# Aux_Outputs.net
KiCad netlist of a schematic drawn in Altium Designer
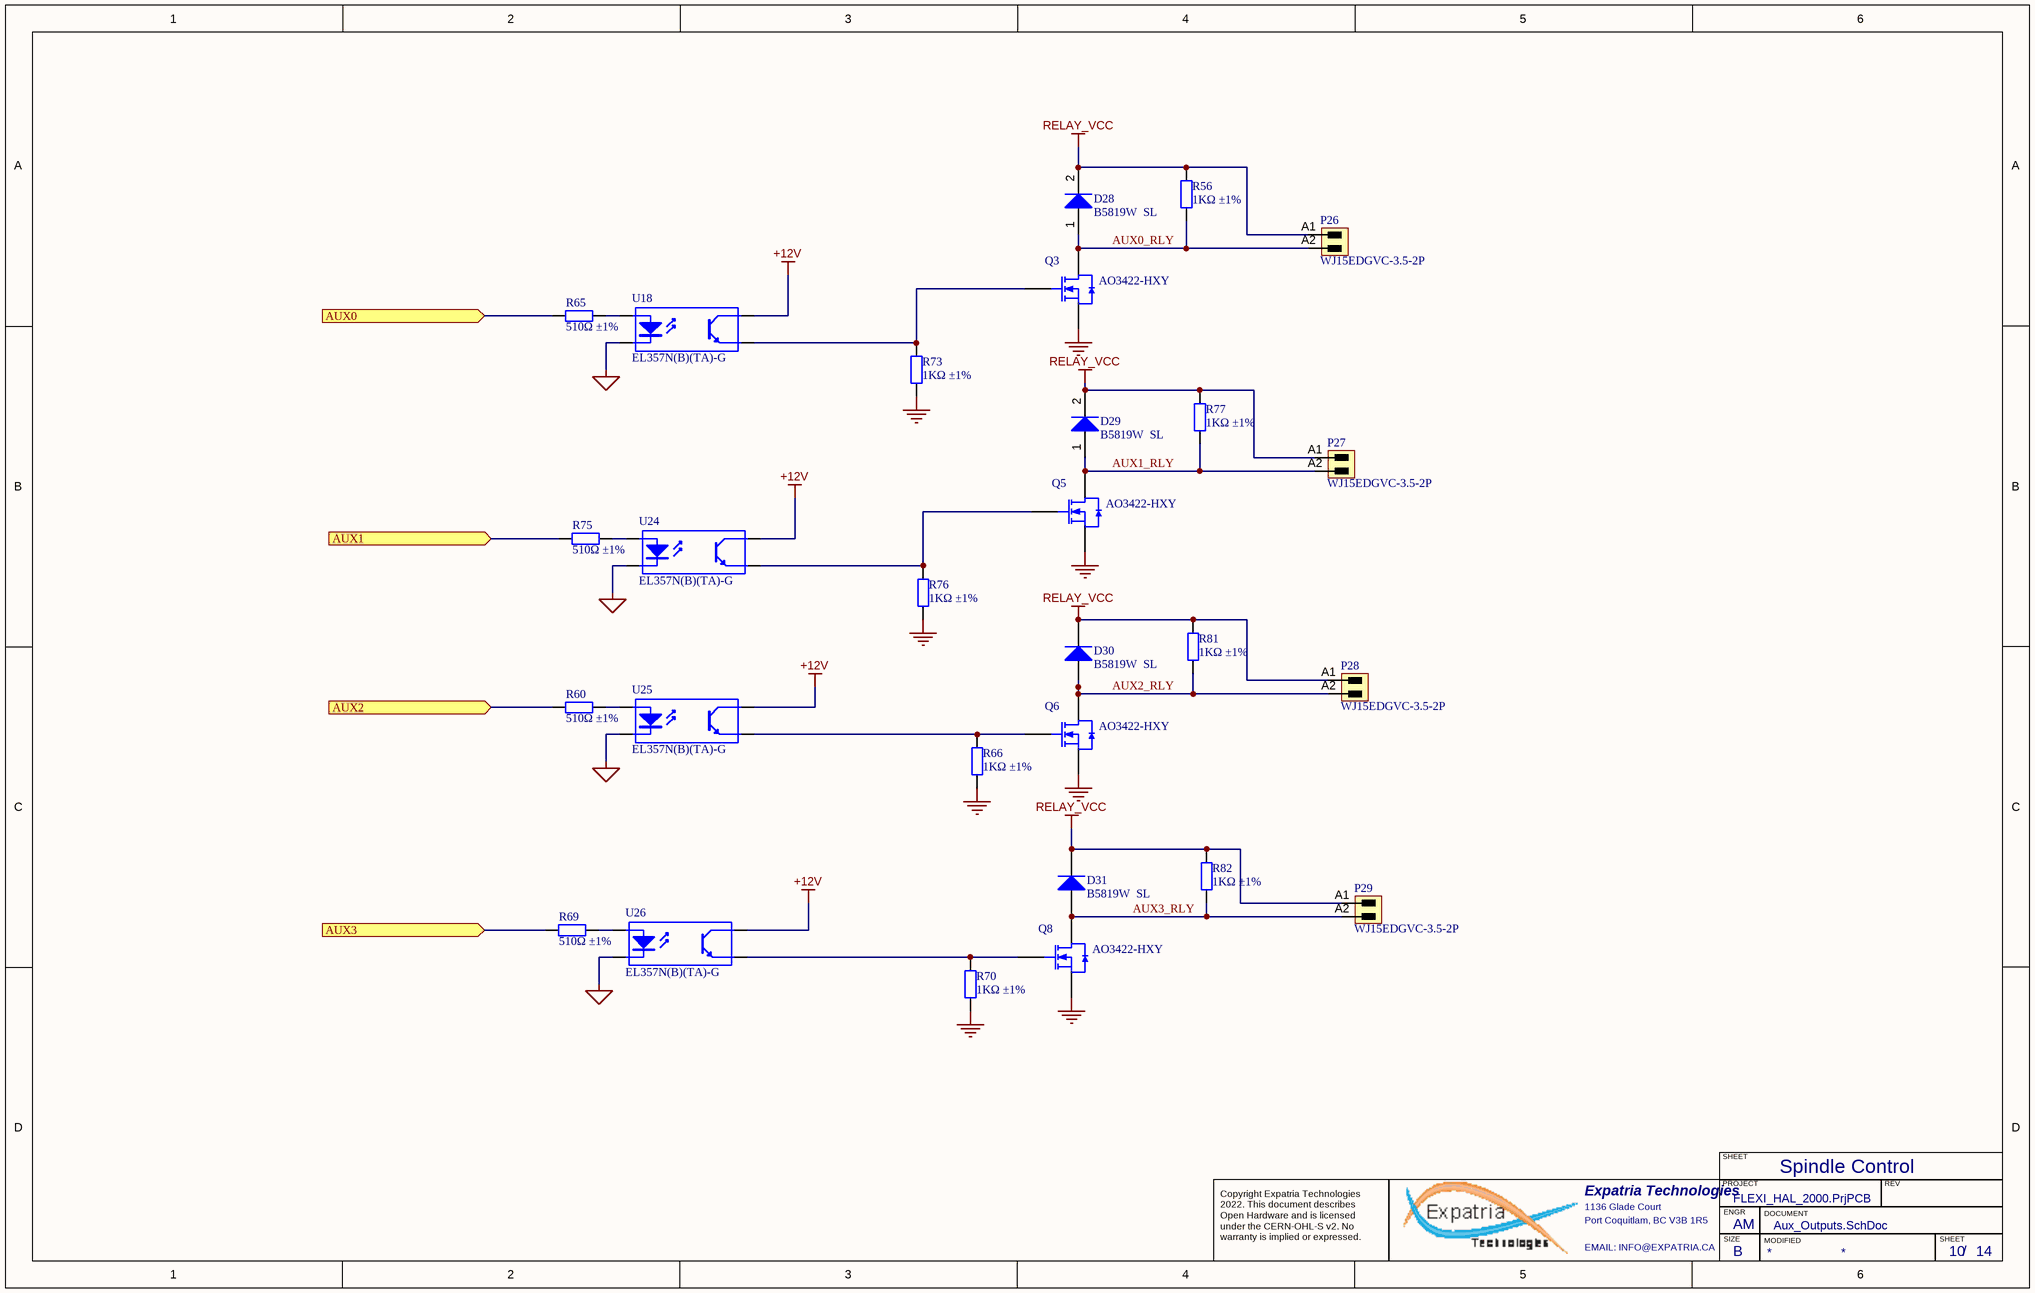
[diagram p0: Aux_Outputs.SchDoc]

(export (version "E")
  (design (tool "Eeschema 10.0.6"))
  (components
    (comp (ref "D28")
      (value "B5819W  SL")
      (footprint "SOD-123")
      (description "Schottky Diode")
      (libsource (lib "Diode") (part "SOD-123 B5819W  SL"))
    )
    (comp (ref "D29")
      (value "B5819W  SL")
      (footprint "SOD-123")
      (description "Schottky Diode")
      (libsource (lib "Diode") (part "SOD-123 B5819W  SL"))
    )
    (comp (ref "D30")
      (value "B5819W  SL")
      (footprint "SOD-123")
      (description "Schottky Diode")
      (libsource (lib "") (part "SOD-123 B5819W  SL_1"))
    )
    (comp (ref "D31")
      (value "B5819W  SL")
      (footprint "SOD-123")
      (description "Schottky Diode")
      (libsource (lib "") (part "SOD-123 B5819W  SL_1"))
    )
    (comp (ref "P26")
      (value "WJ15EDGVC-3.5-2P")
      (footprint "691321100002")
      (fields (field (name "MANUFACTURER") "Weidmueller"))
      (libsource (lib "Universal_CNC_Breakout") (part "3.5mm Terminal Header 2p"))
    )
    (comp (ref "P27")
      (value "WJ15EDGVC-3.5-2P")
      (footprint "691321100002")
      (fields (field (name "MANUFACTURER") "Weidmueller"))
      (libsource (lib "Universal_CNC_Breakout") (part "3.5mm Terminal Header 2p"))
    )
    (comp (ref "P28")
      (value "WJ15EDGVC-3.5-2P")
      (footprint "691321100002")
      (fields (field (name "MANUFACTURER") "Weidmueller"))
      (libsource (lib "Universal_CNC_Breakout") (part "3.5mm Terminal Header 2p"))
    )
    (comp (ref "P29")
      (value "WJ15EDGVC-3.5-2P")
      (footprint "691321100002")
      (fields (field (name "MANUFACTURER") "Weidmueller"))
      (libsource (lib "Universal_CNC_Breakout") (part "3.5mm Terminal Header 2p"))
    )
    (comp (ref "Q3")
      (value "AO3422-HXY")
      (footprint "SOT-23-3L")
      (description "60V 4.5A 8W 75mΩ@10V,5A 2.5V@250uA N Channel 695pF@15V SOT-23-3L MOSFETs ROHS")
      (libsource (lib "MOS") (part "AO3400A N道沟 X0YV1T SOT-23"))
    )
    (comp (ref "Q5")
      (value "AO3422-HXY")
      (footprint "SOT-23-3L")
      (description "60V 4.5A 8W 75mΩ@10V,5A 2.5V@250uA N Channel 695pF@15V SOT-23-3L MOSFETs ROHS")
      (libsource (lib "MOS") (part "AO3400A N道沟 X0YV1T SOT-23"))
    )
    (comp (ref "Q6")
      (value "AO3422-HXY")
      (footprint "SOT-23-3L")
      (description "60V 4.5A 8W 75mΩ@10V,5A 2.5V@250uA N Channel 695pF@15V SOT-23-3L MOSFETs ROHS")
      (libsource (lib "MOS") (part "AO3400A N道沟 X0YV1T SOT-23"))
    )
    (comp (ref "Q8")
      (value "AO3422-HXY")
      (footprint "SOT-23-3L")
      (description "60V 4.5A 8W 75mΩ@10V,5A 2.5V@250uA N Channel 695pF@15V SOT-23-3L MOSFETs ROHS")
      (libsource (lib "MOS") (part "AO3400A N道沟 X0YV1T SOT-23"))
    )
    (comp (ref "R56")
      (value "1KΩ ±1%")
      (footprint "0603_R")
      (description "Chip resistor")
      (fields (field (name "MANUFACTURER") "Uniroyal Elec") (field (name "PARTNUMBER") "0603WAF1001T5E"))
      (libsource (lib "RES") (part "0603 1K (1001) 1%"))
    )
    (comp (ref "R60")
      (value "510Ω ±1%")
      (footprint "0603_R")
      (description "Chip resistor")
      (fields (field (name "MANUFACTURER") "Uniroyal Elec") (field (name "PARTNUMBER") "0603WAF5100T5E"))
      (libsource (lib "RES") (part "0603 510R (5100) 1%"))
    )
    (comp (ref "R65")
      (value "510Ω ±1%")
      (footprint "0603_R")
      (description "Chip resistor")
      (fields (field (name "MANUFACTURER") "Uniroyal Elec") (field (name "PARTNUMBER") "0603WAF5100T5E"))
      (libsource (lib "RES") (part "0603 510R (5100) 1%"))
    )
    (comp (ref "R66")
      (value "1KΩ ±1%")
      (footprint "0603_R")
      (description "Chip resistor")
      (fields (field (name "MANUFACTURER") "Uniroyal Elec") (field (name "PARTNUMBER") "0603WAF1001T5E"))
      (libsource (lib "RES") (part "0603 1K (1001) 1%"))
    )
    (comp (ref "R69")
      (value "510Ω ±1%")
      (footprint "0603_R")
      (description "Chip resistor")
      (fields (field (name "MANUFACTURER") "Uniroyal Elec") (field (name "PARTNUMBER") "0603WAF5100T5E"))
      (libsource (lib "RES") (part "0603 510R (5100) 1%"))
    )
    (comp (ref "R70")
      (value "1KΩ ±1%")
      (footprint "0603_R")
      (description "Chip resistor")
      (fields (field (name "MANUFACTURER") "Uniroyal Elec") (field (name "PARTNUMBER") "0603WAF1001T5E"))
      (libsource (lib "RES") (part "0603 1K (1001) 1%"))
    )
    (comp (ref "R73")
      (value "1KΩ ±1%")
      (footprint "0603_R")
      (description "Chip resistor")
      (fields (field (name "MANUFACTURER") "Uniroyal Elec") (field (name "PARTNUMBER") "0603WAF1001T5E"))
      (libsource (lib "RES") (part "0603 1K (1001) 1%"))
    )
    (comp (ref "R75")
      (value "510Ω ±1%")
      (footprint "0603_R")
      (description "Chip resistor")
      (fields (field (name "MANUFACTURER") "Uniroyal Elec") (field (name "PARTNUMBER") "0603WAF5100T5E"))
      (libsource (lib "RES") (part "0603 510R (5100) 1%"))
    )
    (comp (ref "R76")
      (value "1KΩ ±1%")
      (footprint "0603_R")
      (description "Chip resistor")
      (fields (field (name "MANUFACTURER") "Uniroyal Elec") (field (name "PARTNUMBER") "0603WAF1001T5E"))
      (libsource (lib "RES") (part "0603 1K (1001) 1%"))
    )
    (comp (ref "R77")
      (value "1KΩ ±1%")
      (footprint "0603_R")
      (description "Chip resistor")
      (fields (field (name "MANUFACTURER") "Uniroyal Elec") (field (name "PARTNUMBER") "0603WAF1001T5E"))
      (libsource (lib "RES") (part "0603 1K (1001) 1%"))
    )
    (comp (ref "R81")
      (value "1KΩ ±1%")
      (footprint "0603_R")
      (description "Chip resistor")
      (fields (field (name "MANUFACTURER") "Uniroyal Elec") (field (name "PARTNUMBER") "0603WAF1001T5E"))
      (libsource (lib "RES") (part "0603 1K (1001) 1%"))
    )
    (comp (ref "R82")
      (value "1KΩ ±1%")
      (footprint "0603_R")
      (description "Chip resistor")
      (fields (field (name "MANUFACTURER") "Uniroyal Elec") (field (name "PARTNUMBER") "0603WAF1001T5E"))
      (libsource (lib "RES") (part "0603 1K (1001) 1%"))
    )
    (comp (ref "U18")
      (value "EL357N(B)(TA)-G")
      (footprint "Miscellaneous Devices LC:SOP-4_P2.54")
      (description "Optocoupler SOP-4, EL357N(B)(TA)-G, Everlight Electronics")
      (libsource (lib "IC") (part "EL357N(B)(TA)-G_[C6649]"))
    )
    (comp (ref "U24")
      (value "EL357N(B)(TA)-G")
      (footprint "Miscellaneous Devices LC:SOP-4_P2.54")
      (description "Optocoupler SOP-4, EL357N(B)(TA)-G, Everlight Electronics")
      (libsource (lib "IC") (part "EL357N(B)(TA)-G_[C6649]"))
    )
    (comp (ref "U25")
      (value "EL357N(B)(TA)-G")
      (footprint "Miscellaneous Devices LC:SOP-4_P2.54")
      (description "Optocoupler SOP-4, EL357N(B)(TA)-G, Everlight Electronics")
      (libsource (lib "IC") (part "EL357N(B)(TA)-G_[C6649]"))
    )
    (comp (ref "U26")
      (value "EL357N(B)(TA)-G")
      (footprint "Miscellaneous Devices LC:SOP-4_P2.54")
      (description "Optocoupler SOP-4, EL357N(B)(TA)-G, Everlight Electronics")
      (libsource (lib "IC") (part "EL357N(B)(TA)-G_[C6649]"))
    )
  )
  (nets
    (net (code "1") (name "+12V") (class "Default")
      (node (ref "U18") (pin "4") (pinfunction "C_4") (pintype "passive"))
      (node (ref "U24") (pin "4") (pinfunction "C_4") (pintype "passive"))
      (node (ref "U25") (pin "4") (pinfunction "C_4") (pintype "passive"))
      (node (ref "U26") (pin "4") (pinfunction "C_4") (pintype "passive"))
    )
    (net (code "2") (name "/AUX0") (class "Default")
      (node (ref "R65") (pin "1") (pinfunction "1_1") (pintype "passive"))
    )
    (net (code "3") (name "/AUX0_RLY") (class "Default")
      (node (ref "D28") (pin "1") (pinfunction "A_1") (pintype "passive"))
      (node (ref "P26") (pin "A2") (pinfunction "A2_A2") (pintype "passive"))
      (node (ref "Q3") (pin "3") (pinfunction "D_3") (pintype "passive"))
      (node (ref "R56") (pin "1") (pinfunction "1_1") (pintype "passive"))
    )
    (net (code "4") (name "/AUX1") (class "Default")
      (node (ref "R75") (pin "1") (pinfunction "1_1") (pintype "passive"))
    )
    (net (code "5") (name "/AUX1_RLY") (class "Default")
      (node (ref "D29") (pin "1") (pinfunction "A_1") (pintype "passive"))
      (node (ref "P27") (pin "A2") (pinfunction "A2_A2") (pintype "passive"))
      (node (ref "Q5") (pin "3") (pinfunction "D_3") (pintype "passive"))
      (node (ref "R77") (pin "1") (pinfunction "1_1") (pintype "passive"))
    )
    (net (code "6") (name "/AUX2") (class "Default")
      (node (ref "R60") (pin "1") (pinfunction "1_1") (pintype "passive"))
    )
    (net (code "7") (name "/AUX2_RLY") (class "Default")
      (node (ref "D30") (pin "1") (pinfunction "A_1") (pintype "passive"))
      (node (ref "P28") (pin "A2") (pinfunction "A2_A2") (pintype "passive"))
      (node (ref "Q6") (pin "3") (pinfunction "D_3") (pintype "passive"))
      (node (ref "R81") (pin "1") (pinfunction "1_1") (pintype "passive"))
    )
    (net (code "8") (name "/AUX3") (class "Default")
      (node (ref "R69") (pin "1") (pinfunction "1_1") (pintype "passive"))
    )
    (net (code "9") (name "/AUX3_RLY") (class "Default")
      (node (ref "D31") (pin "1") (pinfunction "A_1") (pintype "passive"))
      (node (ref "P29") (pin "A2") (pinfunction "A2_A2") (pintype "passive"))
      (node (ref "Q8") (pin "3") (pinfunction "D_3") (pintype "passive"))
      (node (ref "R82") (pin "1") (pinfunction "1_1") (pintype "passive"))
    )
    (net (code "10") (name "GND") (class "Default")
      (node (ref "Q3") (pin "2") (pinfunction "S_2") (pintype "passive"))
      (node (ref "Q5") (pin "2") (pinfunction "S_2") (pintype "passive"))
      (node (ref "Q6") (pin "2") (pinfunction "S_2") (pintype "passive"))
      (node (ref "Q8") (pin "2") (pinfunction "S_2") (pintype "passive"))
      (node (ref "R66") (pin "1") (pinfunction "1_1") (pintype "passive"))
      (node (ref "R70") (pin "1") (pinfunction "1_1") (pintype "passive"))
      (node (ref "R73") (pin "1") (pinfunction "1_1") (pintype "passive"))
      (node (ref "R76") (pin "1") (pinfunction "1_1") (pintype "passive"))
    )
    (net (code "11") (name "MCU_GND") (class "Default")
      (node (ref "U18") (pin "2") (pinfunction "K_2") (pintype "passive"))
      (node (ref "U24") (pin "2") (pinfunction "K_2") (pintype "passive"))
      (node (ref "U25") (pin "2") (pinfunction "K_2") (pintype "passive"))
      (node (ref "U26") (pin "2") (pinfunction "K_2") (pintype "passive"))
    )
    (net (code "12") (name "Net-(Q3-G)") (class "Default")
      (node (ref "Q3") (pin "1") (pinfunction "G_1") (pintype "passive"))
      (node (ref "R73") (pin "2") (pinfunction "2_2") (pintype "passive"))
      (node (ref "U18") (pin "3") (pinfunction "E_3") (pintype "passive"))
    )
    (net (code "13") (name "Net-(Q5-G)") (class "Default")
      (node (ref "Q5") (pin "1") (pinfunction "G_1") (pintype "passive"))
      (node (ref "R76") (pin "2") (pinfunction "2_2") (pintype "passive"))
      (node (ref "U24") (pin "3") (pinfunction "E_3") (pintype "passive"))
    )
    (net (code "14") (name "Net-(Q6-G)") (class "Default")
      (node (ref "Q6") (pin "1") (pinfunction "G_1") (pintype "passive"))
      (node (ref "R66") (pin "2") (pinfunction "2_2") (pintype "passive"))
      (node (ref "U25") (pin "3") (pinfunction "E_3") (pintype "passive"))
    )
    (net (code "15") (name "Net-(Q8-G)") (class "Default")
      (node (ref "Q8") (pin "1") (pinfunction "G_1") (pintype "passive"))
      (node (ref "R70") (pin "2") (pinfunction "2_2") (pintype "passive"))
      (node (ref "U26") (pin "3") (pinfunction "E_3") (pintype "passive"))
    )
    (net (code "16") (name "Net-(U18-A)") (class "Default")
      (node (ref "R65") (pin "2") (pinfunction "2_2") (pintype "passive"))
      (node (ref "U18") (pin "1") (pinfunction "A_1") (pintype "passive"))
    )
    (net (code "17") (name "Net-(U24-A)") (class "Default")
      (node (ref "R75") (pin "2") (pinfunction "2_2") (pintype "passive"))
      (node (ref "U24") (pin "1") (pinfunction "A_1") (pintype "passive"))
    )
    (net (code "18") (name "Net-(U25-A)") (class "Default")
      (node (ref "R60") (pin "2") (pinfunction "2_2") (pintype "passive"))
      (node (ref "U25") (pin "1") (pinfunction "A_1") (pintype "passive"))
    )
    (net (code "19") (name "Net-(U26-A)") (class "Default")
      (node (ref "R69") (pin "2") (pinfunction "2_2") (pintype "passive"))
      (node (ref "U26") (pin "1") (pinfunction "A_1") (pintype "passive"))
    )
    (net (code "20") (name "RELAY_VCC") (class "Default")
      (node (ref "D28") (pin "2") (pinfunction "K_2") (pintype "passive"))
      (node (ref "D29") (pin "2") (pinfunction "K_2") (pintype "passive"))
      (node (ref "D30") (pin "2") (pinfunction "K_2") (pintype "passive"))
      (node (ref "D31") (pin "2") (pinfunction "K_2") (pintype "passive"))
      (node (ref "P26") (pin "A1") (pinfunction "A1_A1") (pintype "passive"))
      (node (ref "P27") (pin "A1") (pinfunction "A1_A1") (pintype "passive"))
      (node (ref "P28") (pin "A1") (pinfunction "A1_A1") (pintype "passive"))
      (node (ref "P29") (pin "A1") (pinfunction "A1_A1") (pintype "passive"))
      (node (ref "R56") (pin "2") (pinfunction "2_2") (pintype "passive"))
      (node (ref "R77") (pin "2") (pinfunction "2_2") (pintype "passive"))
      (node (ref "R81") (pin "2") (pinfunction "2_2") (pintype "passive"))
      (node (ref "R82") (pin "2") (pinfunction "2_2") (pintype "passive"))
    )
  )
)
